# Sheet1.net
KiCad netlist of a schematic drawn in Altium Designer
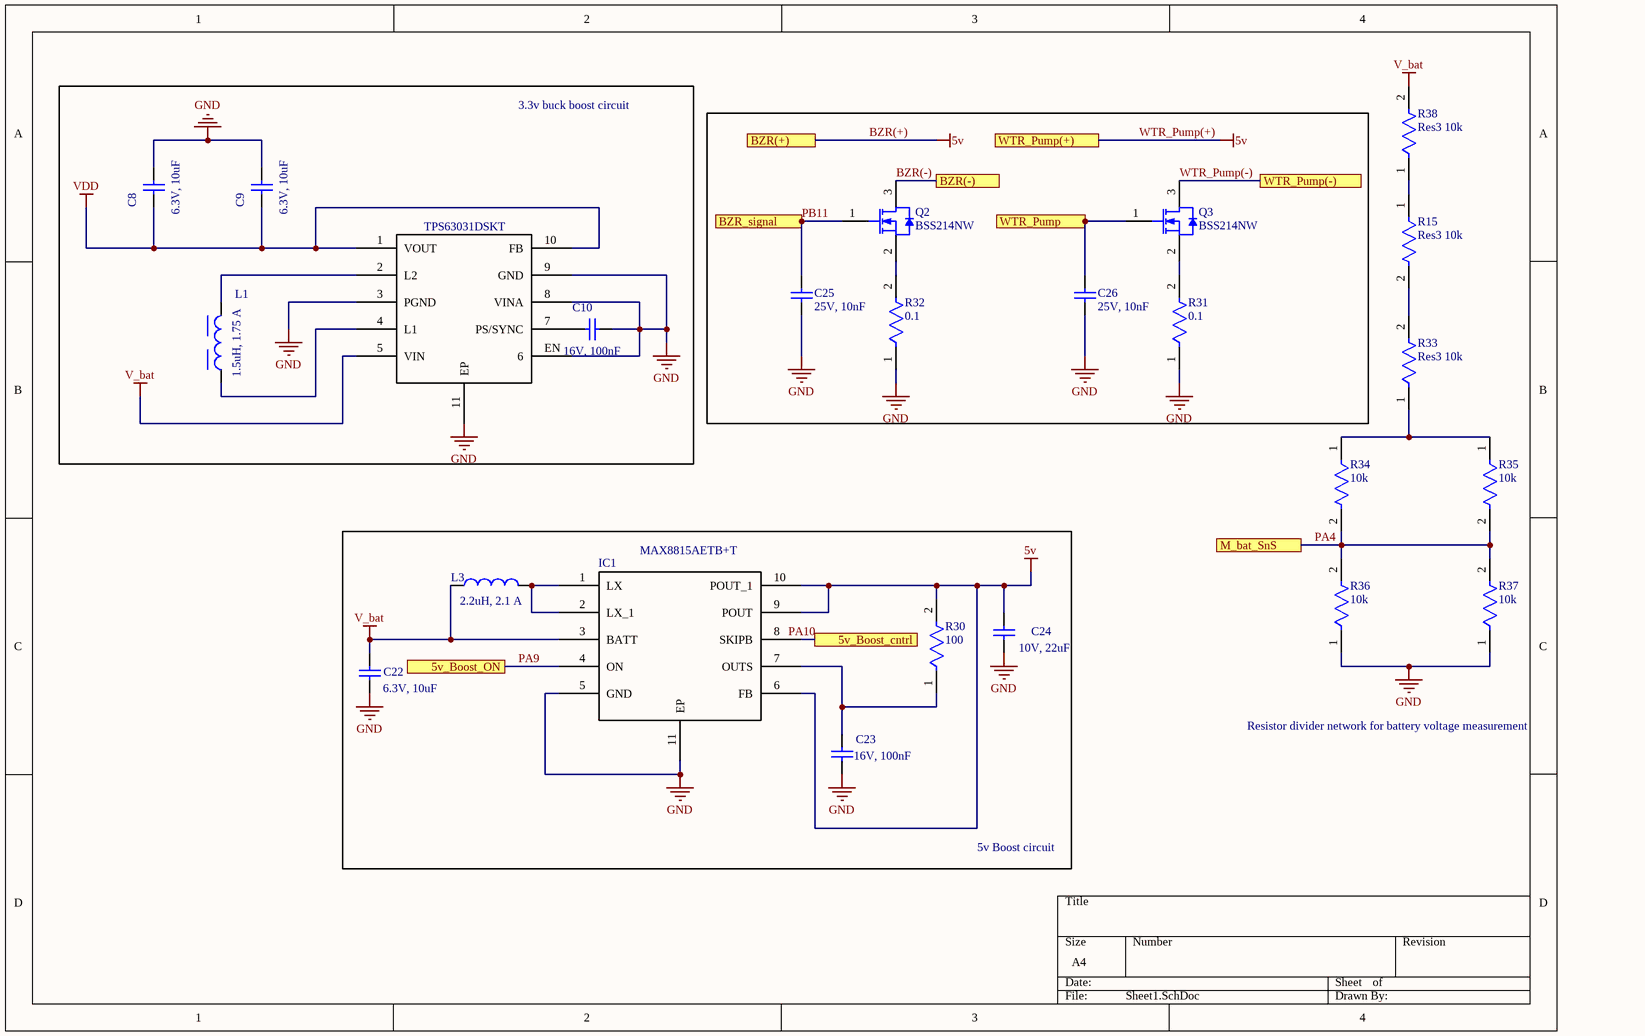
[diagram p0: Sheet1.SchDoc]

(export (version "E")
  (design (tool "Eeschema 10.0.6"))
  (components
    (comp (ref "C8")
      (value "6.3V, 10uF")
      (footprint "WCAP-CSGP_0603_L1.6W0.8H0.8_Reflow")
      (fields (field (name "TOLERANCE") "20%"))
      (libsource (lib "Altium Content Vault") (part "Capacitor_Non-Polarized"))
    )
    (comp (ref "C9")
      (value "6.3V, 10uF")
      (footprint "WCAP-CSGP_0603_L1.6W0.8H0.8_Reflow")
      (fields (field (name "TOLERANCE") "20%"))
      (libsource (lib "Altium Content Vault") (part "Capacitor_Non-Polarized"))
    )
    (comp (ref "C10")
      (value "16V, 100nF")
      (footprint "WCAP-CSGP_0603_L1.6W0.8H0.8_Reflow")
      (description "Cap Ceramic 0.1uF 16V X7R 10% Pad SMD 0603 125C T/R")
      (fields (field (name "TOLERANCE") "10%"))
      (libsource (lib "Altium Content Vault") (part "Capacitor_Non-Polarized"))
    )
    (comp (ref "C22")
      (value "6.3V, 10uF")
      (footprint "WCAP-CSGP_0603_L1.6W0.8H0.8_Reflow")
      (fields (field (name "TOLERANCE") "20%"))
      (libsource (lib "Altium Content Vault") (part "Capacitor_Non-Polarized"))
    )
    (comp (ref "C23")
      (value "16V, 100nF")
      (footprint "WCAP-CSGP_0603_L1.6W0.8H0.8_Reflow")
      (description "Cap Ceramic 0.1uF 16V X7R 10% Pad SMD 0603 125C T/R")
      (fields (field (name "TOLERANCE") "10%"))
      (libsource (lib "Altium Content Vault") (part "Capacitor_Non-Polarized"))
    )
    (comp (ref "C24")
      (value "10V, 22uF")
      (footprint "WCAP-CSGP_0805_L2W1.25H1.25")
      (description "Multilayer Ceramic Capacitor 22uF 0805 2")
      (fields (field (name "TOLERANCE") "20%"))
      (libsource (lib "Altium Content Vault") (part "Capacitor_Non-Polarized"))
    )
    (comp (ref "C25")
      (value "25V, 10nF")
      (footprint "CAPC2013X94X50LL20T25")
      (fields
        (field (name "MANUFACTURER") "AVX Interconnect / Elco")
        (field (name "PART NUMBER") "08053C103JAT2A")
      )
      (libsource (lib "Altium Content Vault") (part "CAP"))
    )
    (comp (ref "C26")
      (value "25V, 10nF")
      (footprint "CAPC2013X94X50LL20T25")
      (fields
        (field (name "MANUFACTURER") "AVX Interconnect / Elco")
        (field (name "PART NUMBER") "08053C103JAT2A")
      )
      (libsource (lib "Altium Content Vault") (part "CAP"))
    )
    (comp (ref "IC1") (value "MAX8815AETB+T") (libsource (lib "Schlib1") (part "MAX8815AETB+T")))
    (comp (ref "L1")
      (value "1.5uH, 1.75 A")
      (footprint "WE-TPC_3816")
      (description "100KHz 125MHz 1.55A 1.75A 1.5μH 47mΩ ±30% standard mounting，SMD mount 3.8mm*3.8mm*1.8mm")
      (fields (field (name "TOLERANCE") "30%"))
      (libsource (lib "Altium Content Vault") (part "Inductor - 3"))
    )
    (comp (ref "L3")
      (value "2.2uH, 2.1 A")
      (footprint "WE-PMCI_322512")
      (description "We-pmci Series 2.2 Uh Multilayer SMD Inductor, 1210 Case, 25MHZ 2.1A 106MO")
      (fields (field (name "TOLERANCE") "20%"))
      (libsource (lib "Altium Content Vault") (part "Inductor - 1"))
    )
    (comp (ref "Q2")
      (value "BSS214NW")
      (footprint "INF-PG-SOT-323_N")
      (fields (field (name "MANUFACTURER") "Infineon"))
      (libsource (lib "Altium Content Vault") (part "INF-NEMOS-GSD-3"))
    )
    (comp (ref "Q3")
      (value "BSS214NW")
      (footprint "INF-PG-SOT-323_N")
      (fields (field (name "MANUFACTURER") "Infineon"))
      (libsource (lib "Altium Content Vault") (part "INF-NEMOS-GSD-3"))
    )
    (comp (ref "R15")
      (value "Res3 10k")
      (footprint "FP-MCT0603-MFG")
      (description "RES SMD 100 OHM 1% 1/8W 0603")
      (libsource (lib "Altium Content Vault") (part "1029c3af85768c4190bb7ad29bc67b5"))
    )
    (comp (ref "R30")
      (value "100")
      (footprint "FP-RT0603-MFG")
      (description "RES SMD 100 OHM 0.1% 1/10W 0603")
      (fields
        (field (name "MANUFACTURER") "Yageo")
        (field (name "MANUFACTURER PART NUMBER") "RT0603BRE07100RL")
      )
      (libsource (lib "Altium Content Vault") (part "1029c3af85768c4190bb7ad29bc67b5"))
    )
    (comp (ref "R31")
      (value "0.1")
      (footprint "FP-RL0603-0_55-MFG")
      (description "RES 0.1 OHM 1% 1/10W 0603")
      (fields (field (name "TOLERANCE") "1%"))
      (libsource (lib "Altium Content Vault") (part "1029c3af85768c4190bb7ad29bc67b5"))
    )
    (comp (ref "R32")
      (value "0.1")
      (footprint "FP-RL0603-0_55-MFG")
      (description "RES 0.1 OHM 1% 1/10W 0603")
      (fields (field (name "TOLERANCE") "1%"))
      (libsource (lib "Altium Content Vault") (part "1029c3af85768c4190bb7ad29bc67b5"))
    )
    (comp (ref "R33")
      (value "Res3 10k")
      (footprint "FP-MCT0603-IPC_B")
      (description "RES SMD 100 OHM 1% 1/8W 0603")
      (libsource (lib "Altium Content Vault") (part "1029c3af85768c4190bb7ad29bc67b5"))
    )
    (comp (ref "R34")
      (value "10k")
      (footprint "FP-MCT0603-MFG")
      (description "RES SMD 100 OHM 1% 1/8W 0603")
      (libsource (lib "Altium Content Vault") (part "1029c3af85768c4190bb7ad29bc67b5"))
    )
    (comp (ref "R35")
      (value "10k")
      (footprint "FP-MCT0603-MFG")
      (description "RES SMD 100 OHM 1% 1/8W 0603")
      (libsource (lib "Altium Content Vault") (part "1029c3af85768c4190bb7ad29bc67b5"))
    )
    (comp (ref "R36")
      (value "10k")
      (footprint "FP-MCT0603-MFG")
      (description "RES SMD 100 OHM 1% 1/8W 0603")
      (libsource (lib "Altium Content Vault") (part "1029c3af85768c4190bb7ad29bc67b5"))
    )
    (comp (ref "R37")
      (value "10k")
      (footprint "FP-MCT0603-MFG")
      (description "RES SMD 100 OHM 1% 1/8W 0603")
      (libsource (lib "Altium Content Vault") (part "1029c3af85768c4190bb7ad29bc67b5"))
    )
    (comp (ref "R38")
      (value "Res3 10k")
      (footprint "FP-MCT0603-MFG")
      (description "RES SMD 100 OHM 1% 1/8W 0603")
      (libsource (lib "Altium Content Vault") (part "1029c3af85768c4190bb7ad29bc67b5"))
    )
    (comp (ref "U3")
      (value "TPS63031DSKT")
      (footprint "R_0603")
      (description "High Efficient Single Inductor Buck-Boost Converter with 1-A Switches 10-SON -40 to 125")
      (libsource (lib "Schlib1") (part "TPS63031DSKT"))
    )
  )
  (nets
    (net (code "1") (name "/5v_Boost_cntrl") (class "Default")
      (node (ref "IC1") (pin "8") (pinfunction "SKIPB_8") (pintype "passive"))
    )
    (net (code "2") (name "/BZR(-)") (class "Default")
      (node (ref "Q2") (pin "3") (pinfunction "DRAIN_3") (pintype "passive"))
    )
    (net (code "3") (name "/PA4") (class "Default")
      (node (ref "R34") (pin "2") (pinfunction "2_2") (pintype "passive"))
      (node (ref "R35") (pin "2") (pinfunction "2_2") (pintype "passive"))
      (node (ref "R36") (pin "2") (pinfunction "2_2") (pintype "passive"))
      (node (ref "R37") (pin "2") (pinfunction "2_2") (pintype "passive"))
    )
    (net (code "4") (name "/PA9") (class "Default")
      (node (ref "IC1") (pin "4") (pinfunction "ON_4") (pintype "passive"))
    )
    (net (code "6") (name "/PB11") (class "Default")
      (node (ref "C25") (pin "2") (pinfunction "2_2") (pintype "passive"))
      (node (ref "Q2") (pin "1") (pinfunction "GATE_1") (pintype "passive"))
    )
    (net (code "7") (name "/WTR_Pump") (class "Default")
      (node (ref "C26") (pin "2") (pinfunction "2_2") (pintype "passive"))
      (node (ref "Q3") (pin "1") (pinfunction "GATE_1") (pintype "passive"))
    )
    (net (code "8") (name "/WTR_Pump(-)") (class "Default")
      (node (ref "Q3") (pin "3") (pinfunction "DRAIN_3") (pintype "passive"))
    )
    (net (code "9") (name "5v") (class "Default")
      (node (ref "C24") (pin "2") (pinfunction "2_2") (pintype "passive"))
      (node (ref "IC1") (pin "10") (pinfunction "POUT_1_10") (pintype "passive"))
      (node (ref "IC1") (pin "6") (pinfunction "FB_6") (pintype "passive"))
      (node (ref "IC1") (pin "9") (pinfunction "POUT_9") (pintype "passive"))
      (node (ref "R30") (pin "2") (pinfunction "2_2") (pintype "passive"))
    )
    (net (code "10") (name "GND") (class "Default")
      (node (ref "C10") (pin "2") (pinfunction "2_2") (pintype "passive"))
      (node (ref "C22") (pin "1") (pinfunction "1_1") (pintype "passive"))
      (node (ref "C23") (pin "1") (pinfunction "1_1") (pintype "passive"))
      (node (ref "C24") (pin "1") (pinfunction "1_1") (pintype "passive"))
      (node (ref "C25") (pin "1") (pinfunction "1_1") (pintype "passive"))
      (node (ref "C26") (pin "1") (pinfunction "1_1") (pintype "passive"))
      (node (ref "C8") (pin "2") (pinfunction "2_2") (pintype "passive"))
      (node (ref "C9") (pin "2") (pinfunction "2_2") (pintype "passive"))
      (node (ref "IC1") (pin "11") (pinfunction "EP_11") (pintype "passive"))
      (node (ref "IC1") (pin "5") (pinfunction "GND_5") (pintype "passive"))
      (node (ref "R31") (pin "1") (pinfunction "1_1") (pintype "passive"))
      (node (ref "R32") (pin "1") (pinfunction "1_1") (pintype "passive"))
      (node (ref "R36") (pin "1") (pinfunction "1_1") (pintype "passive"))
      (node (ref "R37") (pin "1") (pinfunction "1_1") (pintype "passive"))
      (node (ref "U3") (pin "11") (pinfunction "EP_11") (pintype "passive"))
      (node (ref "U3") (pin "3") (pinfunction "PGND_3") (pintype "passive"))
      (node (ref "U3") (pin "8") (pinfunction "VINA_8") (pintype "passive"))
      (node (ref "U3") (pin "9") (pinfunction "GND_9") (pintype "passive"))
      (node (ref "U3") (pin "EN") (pinfunction "6_EN") (pintype "passive"))
    )
    (net (code "11") (name "Net-(IC1-LX)") (class "Default")
      (node (ref "IC1") (pin "1") (pinfunction "LX_1") (pintype "passive"))
      (node (ref "IC1") (pin "2") (pinfunction "LX_1_2") (pintype "passive"))
      (node (ref "L3") (pin "2") (pinfunction "2_2") (pintype "passive"))
    )
    (net (code "12") (name "Net-(IC1-OUTS)") (class "Default")
      (node (ref "C23") (pin "2") (pinfunction "2_2") (pintype "passive"))
      (node (ref "IC1") (pin "7") (pinfunction "OUTS_7") (pintype "passive"))
      (node (ref "R30") (pin "1") (pinfunction "1_1") (pintype "passive"))
    )
    (net (code "13") (name "Net-(Q2-SOURCE)") (class "Default")
      (node (ref "Q2") (pin "2") (pinfunction "SOURCE_2") (pintype "passive"))
      (node (ref "R32") (pin "2") (pinfunction "2_2") (pintype "passive"))
    )
    (net (code "14") (name "Net-(Q3-SOURCE)") (class "Default")
      (node (ref "Q3") (pin "2") (pinfunction "SOURCE_2") (pintype "passive"))
      (node (ref "R31") (pin "2") (pinfunction "2_2") (pintype "passive"))
    )
    (net (code "15") (name "Net-(R15-Pad1)") (class "Default")
      (node (ref "R15") (pin "1") (pinfunction "1_1") (pintype "passive"))
      (node (ref "R38") (pin "1") (pinfunction "1_1") (pintype "passive"))
    )
    (net (code "16") (name "Net-(R15-Pad2)") (class "Default")
      (node (ref "R15") (pin "2") (pinfunction "2_2") (pintype "passive"))
      (node (ref "R33") (pin "2") (pinfunction "2_2") (pintype "passive"))
    )
    (net (code "17") (name "Net-(R33-Pad1)") (class "Default")
      (node (ref "R33") (pin "1") (pinfunction "1_1") (pintype "passive"))
      (node (ref "R34") (pin "1") (pinfunction "1_1") (pintype "passive"))
      (node (ref "R35") (pin "1") (pinfunction "1_1") (pintype "passive"))
    )
    (net (code "18") (name "Net-(U3-L1)") (class "Default")
      (node (ref "L1") (pin "1") (pinfunction "1_1") (pintype "passive"))
      (node (ref "U3") (pin "4") (pinfunction "L1_4") (pintype "passive"))
    )
    (net (code "19") (name "Net-(U3-L2)") (class "Default")
      (node (ref "L1") (pin "2") (pinfunction "2_2") (pintype "passive"))
      (node (ref "U3") (pin "2") (pinfunction "L2_2") (pintype "passive"))
    )
    (net (code "20") (name "Net-(U3-PS{slash}SYNC)") (class "Default")
      (node (ref "C10") (pin "1") (pinfunction "1_1") (pintype "passive"))
      (node (ref "U3") (pin "7") (pinfunction "PS/SYNC_7") (pintype "passive"))
    )
    (net (code "21") (name "VDD") (class "Default")
      (node (ref "C8") (pin "1") (pinfunction "1_1") (pintype "passive"))
      (node (ref "C9") (pin "1") (pinfunction "1_1") (pintype "passive"))
      (node (ref "U3") (pin "1") (pinfunction "VOUT_1") (pintype "passive"))
      (node (ref "U3") (pin "10") (pinfunction "FB_10") (pintype "passive"))
    )
    (net (code "22") (name "V_bat") (class "Default")
      (node (ref "C22") (pin "2") (pinfunction "2_2") (pintype "passive"))
      (node (ref "IC1") (pin "3") (pinfunction "BATT_3") (pintype "passive"))
      (node (ref "L3") (pin "1") (pinfunction "1_1") (pintype "passive"))
      (node (ref "R38") (pin "2") (pinfunction "2_2") (pintype "passive"))
      (node (ref "U3") (pin "5") (pinfunction "VIN_5") (pintype "passive"))
    )
  )
)
